# MultiChannelFlex_LED.net
KiCad netlist of a schematic drawn in Altium Designer
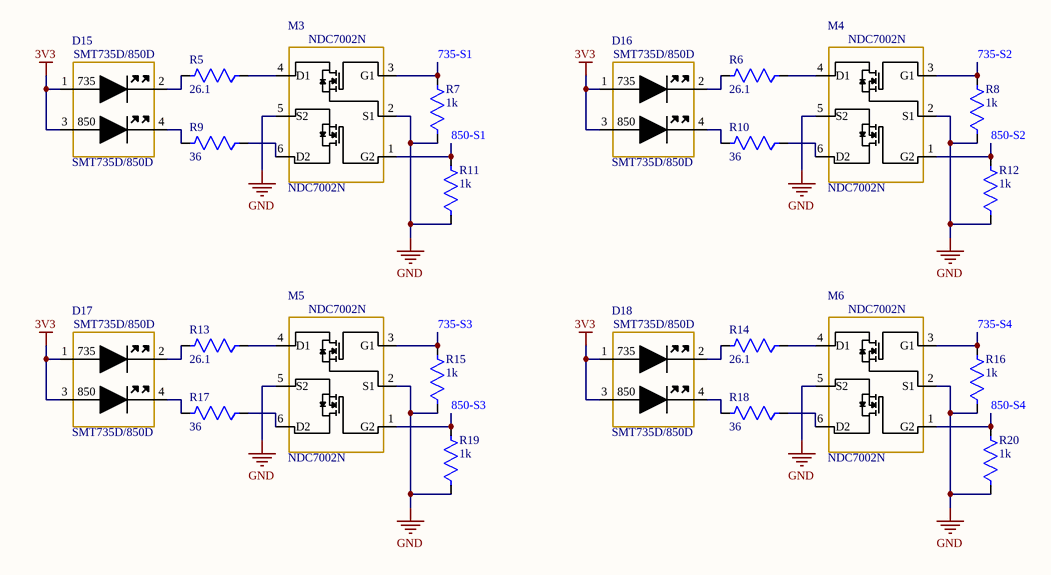
[diagram p0: MultiChannelFlex_LED.SchDoc]

(export (version "E")
  (design (tool "Eeschema 10.0.6"))
  (components
    (comp (ref "D15")
      (value "SMT735D/850D")
      (footprint "SMT735D_850D")
      (libsource (lib "Single_Channel_fNIRS") (part "SMT735D/850D"))
    )
    (comp (ref "D16")
      (value "SMT735D/850D")
      (footprint "SMT735D_850D")
      (libsource (lib "Single_Channel_fNIRS") (part "SMT735D/850D"))
    )
    (comp (ref "D17")
      (value "SMT735D/850D")
      (footprint "SMT735D_850D")
      (libsource (lib "Single_Channel_fNIRS") (part "SMT735D/850D"))
    )
    (comp (ref "D18")
      (value "SMT735D/850D")
      (footprint "SMT735D_850D")
      (libsource (lib "Single_Channel_fNIRS") (part "SMT735D/850D"))
    )
    (comp (ref "M3")
      (value "NDC7002N")
      (footprint "FAIR-MA06A_V")
      (libsource (lib "Single_Channel_fNIRS") (part "NDC7002N"))
    )
    (comp (ref "M4")
      (value "NDC7002N")
      (footprint "FAIR-MA06A_V")
      (libsource (lib "Single_Channel_fNIRS") (part "NDC7002N"))
    )
    (comp (ref "M5")
      (value "NDC7002N")
      (footprint "FAIR-MA06A_V")
      (libsource (lib "Single_Channel_fNIRS") (part "NDC7002N"))
    )
    (comp (ref "M6")
      (value "NDC7002N")
      (footprint "FAIR-MA06A_V")
      (libsource (lib "Single_Channel_fNIRS") (part "NDC7002N"))
    )
    (comp (ref "R5")
      (value "26.1")
      (footprint "R1206")
      (description "1206 26.1 Ohm")
      (fields
        (field (name "OCTOPART") "https://octopart.com/rq73c2b26r1btd-te+connectivity-93911368")
        (field (name "MANUFACTURER PART NUMBER") "RQ73C2B26R1BTD")
      )
      (libsource (lib "Single_Channel_fNIRS") (part "RQ73C2B26R1BTD"))
    )
    (comp (ref "R6")
      (value "26.1")
      (footprint "R1206")
      (description "1206 26.1 Ohm")
      (fields
        (field (name "OCTOPART") "https://octopart.com/rq73c2b26r1btd-te+connectivity-93911368")
        (field (name "MANUFACTURER PART NUMBER") "RQ73C2B26R1BTD")
      )
      (libsource (lib "Single_Channel_fNIRS") (part "RQ73C2B26R1BTD"))
    )
    (comp (ref "R7")
      (value "1k")
      (footprint "R1206")
      (description "1206 1kOhm")
      (libsource (lib "Single_Channel_fNIRS") (part "RT1206BRD071KL"))
    )
    (comp (ref "R8")
      (value "1k")
      (footprint "R1206")
      (description "1206 1kOhm")
      (libsource (lib "Single_Channel_fNIRS") (part "RT1206BRD071KL"))
    )
    (comp (ref "R9")
      (value "36")
      (footprint "R1206")
      (description "1206 36 Ohm")
      (fields
        (field (name "MANUFACTURER") "Yageo")
        (field (name "MANUFACTURER PART NUMBER") "RT1206BRD0736RL")
      )
      (libsource (lib "Single_Channel_fNIRS") (part "RT1206BRD0736RL"))
    )
    (comp (ref "R10")
      (value "36")
      (footprint "R1206")
      (description "1206 36 Ohm")
      (fields
        (field (name "MANUFACTURER") "Yageo")
        (field (name "MANUFACTURER PART NUMBER") "RT1206BRD0736RL")
      )
      (libsource (lib "Single_Channel_fNIRS") (part "RT1206BRD0736RL"))
    )
    (comp (ref "R11")
      (value "1k")
      (footprint "R1206")
      (description "1206 1kOhm")
      (libsource (lib "Single_Channel_fNIRS") (part "RT1206BRD071KL"))
    )
    (comp (ref "R12")
      (value "1k")
      (footprint "R1206")
      (description "1206 1kOhm")
      (libsource (lib "Single_Channel_fNIRS") (part "RT1206BRD071KL"))
    )
    (comp (ref "R13")
      (value "26.1")
      (footprint "R1206")
      (description "1206 26.1 Ohm")
      (fields
        (field (name "OCTOPART") "https://octopart.com/rq73c2b26r1btd-te+connectivity-93911368")
        (field (name "MANUFACTURER PART NUMBER") "RQ73C2B26R1BTD")
      )
      (libsource (lib "Single_Channel_fNIRS") (part "RQ73C2B26R1BTD"))
    )
    (comp (ref "R14")
      (value "26.1")
      (footprint "R1206")
      (description "1206 26.1 Ohm")
      (fields
        (field (name "OCTOPART") "https://octopart.com/rq73c2b26r1btd-te+connectivity-93911368")
        (field (name "MANUFACTURER PART NUMBER") "RQ73C2B26R1BTD")
      )
      (libsource (lib "Single_Channel_fNIRS") (part "RQ73C2B26R1BTD"))
    )
    (comp (ref "R15")
      (value "1k")
      (footprint "R1206")
      (description "1206 1kOhm")
      (libsource (lib "Single_Channel_fNIRS") (part "RT1206BRD071KL"))
    )
    (comp (ref "R16")
      (value "1k")
      (footprint "R1206")
      (description "1206 1kOhm")
      (libsource (lib "Single_Channel_fNIRS") (part "RT1206BRD071KL"))
    )
    (comp (ref "R17")
      (value "36")
      (footprint "R1206")
      (description "1206 36 Ohm")
      (fields
        (field (name "MANUFACTURER") "Yageo")
        (field (name "MANUFACTURER PART NUMBER") "RT1206BRD0736RL")
      )
      (libsource (lib "Single_Channel_fNIRS") (part "RT1206BRD0736RL"))
    )
    (comp (ref "R18")
      (value "36")
      (footprint "R1206")
      (description "1206 36 Ohm")
      (fields
        (field (name "MANUFACTURER") "Yageo")
        (field (name "MANUFACTURER PART NUMBER") "RT1206BRD0736RL")
      )
      (libsource (lib "Single_Channel_fNIRS") (part "RT1206BRD0736RL"))
    )
    (comp (ref "R19")
      (value "1k")
      (footprint "R1206")
      (description "1206 1kOhm")
      (libsource (lib "Single_Channel_fNIRS") (part "RT1206BRD071KL"))
    )
    (comp (ref "R20")
      (value "1k")
      (footprint "R1206")
      (description "1206 1kOhm")
      (libsource (lib "Single_Channel_fNIRS") (part "RT1206BRD071KL"))
    )
  )
  (nets
    (net (code "1") (name "/735-S1") (class "Default")
      (node (ref "M3") (pin "3") (pinfunction "G1_3") (pintype "passive"))
      (node (ref "R7") (pin "2") (pinfunction "2_2") (pintype "passive"))
    )
    (net (code "2") (name "/735-S2") (class "Default")
      (node (ref "M4") (pin "3") (pinfunction "G1_3") (pintype "passive"))
      (node (ref "R8") (pin "2") (pinfunction "2_2") (pintype "passive"))
    )
    (net (code "3") (name "/735-S3") (class "Default")
      (node (ref "M5") (pin "3") (pinfunction "G1_3") (pintype "passive"))
      (node (ref "R15") (pin "2") (pinfunction "2_2") (pintype "passive"))
    )
    (net (code "4") (name "/735-S4") (class "Default")
      (node (ref "M6") (pin "3") (pinfunction "G1_3") (pintype "passive"))
      (node (ref "R16") (pin "2") (pinfunction "2_2") (pintype "passive"))
    )
    (net (code "5") (name "/850-S1") (class "Default")
      (node (ref "M3") (pin "1") (pinfunction "G2_1") (pintype "passive"))
      (node (ref "R11") (pin "2") (pinfunction "2_2") (pintype "passive"))
    )
    (net (code "6") (name "/850-S2") (class "Default")
      (node (ref "M4") (pin "1") (pinfunction "G2_1") (pintype "passive"))
      (node (ref "R12") (pin "2") (pinfunction "2_2") (pintype "passive"))
    )
    (net (code "7") (name "/850-S3") (class "Default")
      (node (ref "M5") (pin "1") (pinfunction "G2_1") (pintype "passive"))
      (node (ref "R19") (pin "2") (pinfunction "2_2") (pintype "passive"))
    )
    (net (code "8") (name "/850-S4") (class "Default")
      (node (ref "M6") (pin "1") (pinfunction "G2_1") (pintype "passive"))
      (node (ref "R20") (pin "2") (pinfunction "2_2") (pintype "passive"))
    )
    (net (code "9") (name "3V3") (class "Default")
      (node (ref "D15") (pin "1") (pinfunction "1_1") (pintype "passive"))
      (node (ref "D15") (pin "3") (pinfunction "3_3") (pintype "passive"))
      (node (ref "D16") (pin "1") (pinfunction "1_1") (pintype "passive"))
      (node (ref "D16") (pin "3") (pinfunction "3_3") (pintype "passive"))
      (node (ref "D17") (pin "1") (pinfunction "1_1") (pintype "passive"))
      (node (ref "D17") (pin "3") (pinfunction "3_3") (pintype "passive"))
      (node (ref "D18") (pin "1") (pinfunction "1_1") (pintype "passive"))
      (node (ref "D18") (pin "3") (pinfunction "3_3") (pintype "passive"))
    )
    (net (code "10") (name "GND") (class "Default")
      (node (ref "M3") (pin "2") (pinfunction "S1_2") (pintype "passive"))
      (node (ref "M3") (pin "5") (pinfunction "S2_5") (pintype "passive"))
      (node (ref "M4") (pin "2") (pinfunction "S1_2") (pintype "passive"))
      (node (ref "M4") (pin "5") (pinfunction "S2_5") (pintype "passive"))
      (node (ref "M5") (pin "2") (pinfunction "S1_2") (pintype "passive"))
      (node (ref "M5") (pin "5") (pinfunction "S2_5") (pintype "passive"))
      (node (ref "M6") (pin "2") (pinfunction "S1_2") (pintype "passive"))
      (node (ref "M6") (pin "5") (pinfunction "S2_5") (pintype "passive"))
      (node (ref "R11") (pin "1") (pinfunction "1_1") (pintype "passive"))
      (node (ref "R12") (pin "1") (pinfunction "1_1") (pintype "passive"))
      (node (ref "R15") (pin "1") (pinfunction "1_1") (pintype "passive"))
      (node (ref "R16") (pin "1") (pinfunction "1_1") (pintype "passive"))
      (node (ref "R19") (pin "1") (pinfunction "1_1") (pintype "passive"))
      (node (ref "R20") (pin "1") (pinfunction "1_1") (pintype "passive"))
      (node (ref "R7") (pin "1") (pinfunction "1_1") (pintype "passive"))
      (node (ref "R8") (pin "1") (pinfunction "1_1") (pintype "passive"))
    )
    (net (code "11") (name "Net-(D15-Pad2)") (class "Default")
      (node (ref "D15") (pin "2") (pinfunction "2_2") (pintype "passive"))
      (node (ref "R5") (pin "2") (pinfunction "2_2") (pintype "passive"))
    )
    (net (code "12") (name "Net-(D15-Pad4)") (class "Default")
      (node (ref "D15") (pin "4") (pinfunction "4_4") (pintype "passive"))
      (node (ref "R9") (pin "2") (pinfunction "2_2") (pintype "passive"))
    )
    (net (code "13") (name "Net-(D16-Pad2)") (class "Default")
      (node (ref "D16") (pin "2") (pinfunction "2_2") (pintype "passive"))
      (node (ref "R6") (pin "2") (pinfunction "2_2") (pintype "passive"))
    )
    (net (code "14") (name "Net-(D16-Pad4)") (class "Default")
      (node (ref "D16") (pin "4") (pinfunction "4_4") (pintype "passive"))
      (node (ref "R10") (pin "2") (pinfunction "2_2") (pintype "passive"))
    )
    (net (code "15") (name "Net-(D17-Pad2)") (class "Default")
      (node (ref "D17") (pin "2") (pinfunction "2_2") (pintype "passive"))
      (node (ref "R13") (pin "2") (pinfunction "2_2") (pintype "passive"))
    )
    (net (code "16") (name "Net-(D17-Pad4)") (class "Default")
      (node (ref "D17") (pin "4") (pinfunction "4_4") (pintype "passive"))
      (node (ref "R17") (pin "2") (pinfunction "2_2") (pintype "passive"))
    )
    (net (code "17") (name "Net-(D18-Pad2)") (class "Default")
      (node (ref "D18") (pin "2") (pinfunction "2_2") (pintype "passive"))
      (node (ref "R14") (pin "2") (pinfunction "2_2") (pintype "passive"))
    )
    (net (code "18") (name "Net-(D18-Pad4)") (class "Default")
      (node (ref "D18") (pin "4") (pinfunction "4_4") (pintype "passive"))
      (node (ref "R18") (pin "2") (pinfunction "2_2") (pintype "passive"))
    )
    (net (code "19") (name "Net-(M3-D1)") (class "Default")
      (node (ref "M3") (pin "4") (pinfunction "D1_4") (pintype "passive"))
      (node (ref "R5") (pin "1") (pinfunction "1_1") (pintype "passive"))
    )
    (net (code "20") (name "Net-(M3-D2)") (class "Default")
      (node (ref "M3") (pin "6") (pinfunction "D2_6") (pintype "passive"))
      (node (ref "R9") (pin "1") (pinfunction "1_1") (pintype "passive"))
    )
    (net (code "21") (name "Net-(M4-D1)") (class "Default")
      (node (ref "M4") (pin "4") (pinfunction "D1_4") (pintype "passive"))
      (node (ref "R6") (pin "1") (pinfunction "1_1") (pintype "passive"))
    )
    (net (code "22") (name "Net-(M4-D2)") (class "Default")
      (node (ref "M4") (pin "6") (pinfunction "D2_6") (pintype "passive"))
      (node (ref "R10") (pin "1") (pinfunction "1_1") (pintype "passive"))
    )
    (net (code "23") (name "Net-(M5-D1)") (class "Default")
      (node (ref "M5") (pin "4") (pinfunction "D1_4") (pintype "passive"))
      (node (ref "R13") (pin "1") (pinfunction "1_1") (pintype "passive"))
    )
    (net (code "24") (name "Net-(M5-D2)") (class "Default")
      (node (ref "M5") (pin "6") (pinfunction "D2_6") (pintype "passive"))
      (node (ref "R17") (pin "1") (pinfunction "1_1") (pintype "passive"))
    )
    (net (code "25") (name "Net-(M6-D1)") (class "Default")
      (node (ref "M6") (pin "4") (pinfunction "D1_4") (pintype "passive"))
      (node (ref "R14") (pin "1") (pinfunction "1_1") (pintype "passive"))
    )
    (net (code "26") (name "Net-(M6-D2)") (class "Default")
      (node (ref "M6") (pin "6") (pinfunction "D2_6") (pintype "passive"))
      (node (ref "R18") (pin "1") (pinfunction "1_1") (pintype "passive"))
    )
  )
)
